# Button.net
KiCad netlist of a schematic drawn in EAGLE
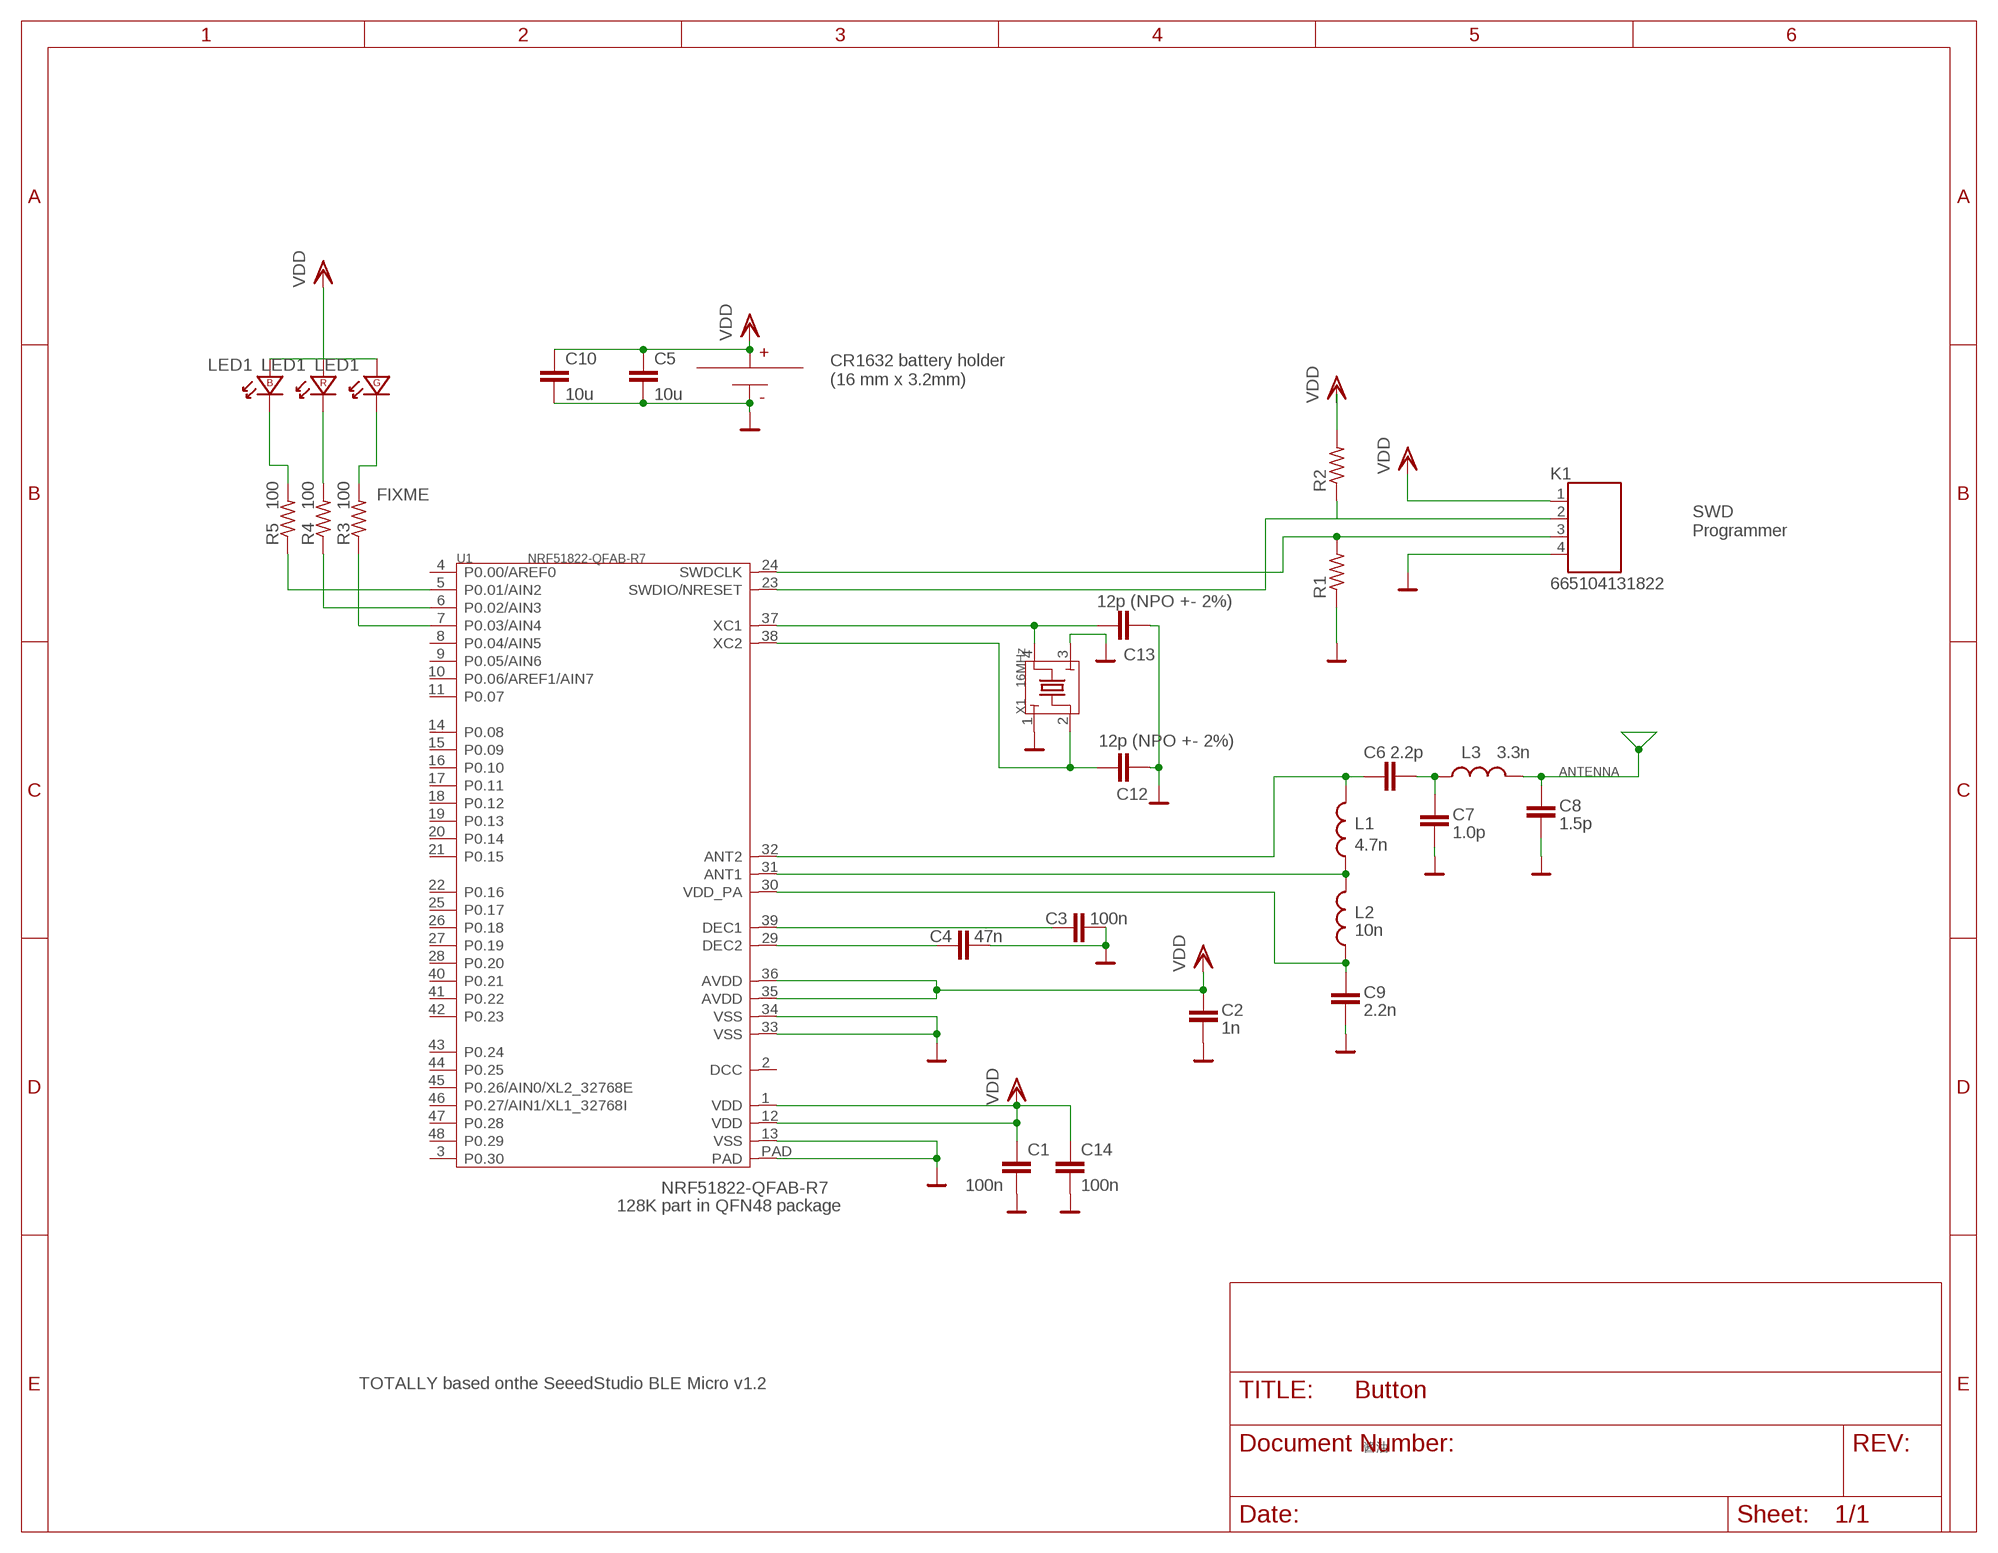
[diagram p0: schematic, sheet 1]

(export (version "E")
  (design (tool "Eeschema 10.0.6"))
  (components
    (comp (ref "B1")
      (value "CON-COINCEL-HOLDER-KEYSTONE-3012TR")
      (footprint "eagle-import:16MM-COINCELL-KEYSTONE")
      (libsource (lib "eagle-import") (part "CON-COINCEL-HOLDER-KEYSTONE-3012TR"))
    )
    (comp (ref "C1")
      (value "100n")
      (footprint "eagle-import:.0402-C-NOSILK")
      (libsource (lib "eagle-import") (part "C-EU0402-C-NOSILK"))
    )
    (comp (ref "C2")
      (value "1n")
      (footprint "eagle-import:.0402-C-NOSILK")
      (libsource (lib "eagle-import") (part "C-EU0402-C-NOSILK"))
    )
    (comp (ref "C3")
      (value "100n")
      (footprint "eagle-import:.0402-C-NOSILK")
      (libsource (lib "eagle-import") (part "C-EU0402-C-NOSILK"))
    )
    (comp (ref "C4")
      (value "47n")
      (footprint "eagle-import:.0402-C-NOSILK")
      (libsource (lib "eagle-import") (part "C-EU0402-C-NOSILK"))
    )
    (comp (ref "C5")
      (value "10u")
      (footprint "eagle-import:.0805-B-NOSILK")
      (libsource (lib "eagle-import") (part "C-EU0805-B-NOSILK"))
    )
    (comp (ref "C6")
      (value "2.2p")
      (footprint "eagle-import:.0402-C-NOSILK")
      (libsource (lib "eagle-import") (part "C-EU0402-C-NOSILK"))
    )
    (comp (ref "C7")
      (value "1.0p")
      (footprint "eagle-import:.0402-C-NOSILK")
      (libsource (lib "eagle-import") (part "C-EU0402-C-NOSILK"))
    )
    (comp (ref "C8")
      (value "1.5p")
      (footprint "eagle-import:.0402-C-NOSILK")
      (libsource (lib "eagle-import") (part "C-EU0402-C-NOSILK"))
    )
    (comp (ref "C9")
      (value "2.2n")
      (footprint "eagle-import:.0402-C-NOSILK")
      (libsource (lib "eagle-import") (part "C-EU0402-C-NOSILK"))
    )
    (comp (ref "C10")
      (value "10u")
      (footprint "eagle-import:.0805-B-NOSILK")
      (libsource (lib "eagle-import") (part "C-EU0805-B-NOSILK"))
    )
    (comp (ref "C12")
      (value "12p (NPO +- 2%)")
      (footprint "eagle-import:.0402-C-NOSILK")
      (libsource (lib "eagle-import") (part "C-EU0402-C-NOSILK"))
    )
    (comp (ref "C13")
      (value "12p (NPO +- 2%)")
      (footprint "eagle-import:.0402-C-NOSILK")
      (libsource (lib "eagle-import") (part "C-EU0402-C-NOSILK"))
    )
    (comp (ref "C14")
      (value "100n")
      (footprint "eagle-import:.0402-C-NOSILK")
      (libsource (lib "eagle-import") (part "C-EU0402-C-NOSILK"))
    )
    (comp (ref "K1")
      (value "665104131822")
      (footprint "eagle-import:665104131822")
      (libsource (lib "eagle-import") (part "665104131822"))
    )
    (comp (ref "L1")
      (value "4.7n")
      (footprint "eagle-import:.0402-C-NOSILK")
      (libsource (lib "eagle-import") (part "L-US0402-C-NOSILK"))
    )
    (comp (ref "L2")
      (value "10n")
      (footprint "eagle-import:.0402-C-NOSILK")
      (libsource (lib "eagle-import") (part "L-US0402-C-NOSILK"))
    )
    (comp (ref "L3")
      (value "3.3n")
      (footprint "eagle-import:.0402-C-NOSILK")
      (libsource (lib "eagle-import") (part "L-US0402-C-NOSILK"))
    )
    (comp (ref "LED1")
      (value "LED-RGB-SEPARATE-3528")
      (footprint "eagle-import:LED-3528")
      (libsource (lib "eagle-import") (part "LED-RGB-SEPARATE-3528"))
    )
    (comp (ref "R1")
      (value "R-US_R0402")
      (footprint "eagle-import:R0402")
      (libsource (lib "eagle-import") (part "R-US_R0402"))
    )
    (comp (ref "R2")
      (value "R-US_R0402")
      (footprint "eagle-import:R0402")
      (libsource (lib "eagle-import") (part "R-US_R0402"))
    )
    (comp (ref "R3")
      (value "100")
      (footprint "eagle-import:.0402-C-NOSILK")
      (libsource (lib "eagle-import") (part "R-US_0402-C-NOSILK"))
    )
    (comp (ref "R4")
      (value "100")
      (footprint "eagle-import:.0402-C-NOSILK")
      (libsource (lib "eagle-import") (part "R-US_0402-C-NOSILK"))
    )
    (comp (ref "R5")
      (value "100")
      (footprint "eagle-import:.0402-C-NOSILK")
      (libsource (lib "eagle-import") (part "R-US_0402-C-NOSILK"))
    )
    (comp (ref "U1")
      (value "NRF51822-QFAB-R7")
      (footprint "eagle-import:QFN48-6X6MM")
      (libsource (lib "eagle-import") (part "NRF51822"))
    )
    (comp (ref "X1")
      (value "16MHz")
      (footprint "eagle-import:2520")
      (libsource (lib "eagle-import") (part "CRYSTAL'-2520'"))
    )
  )
  (nets
    (net (code "1") (name "/ANTENNA") (class "Default")
      (node (ref "C8") (pin "2") (pinfunction "2_2") (pintype "passive"))
      (node (ref "L3") (pin "2") (pinfunction "2_2") (pintype "passive"))
    )
    (net (code "2") (name "GND") (class "Default")
      (node (ref "B1") (pin "NEG") (pinfunction "NEG_NEG") (pintype "power_in"))
      (node (ref "C1") (pin "2") (pinfunction "2_2") (pintype "passive"))
      (node (ref "C10") (pin "2") (pinfunction "2_2") (pintype "passive"))
      (node (ref "C12") (pin "2") (pinfunction "2_2") (pintype "passive"))
      (node (ref "C13") (pin "2") (pinfunction "2_2") (pintype "passive"))
      (node (ref "C14") (pin "2") (pinfunction "2_2") (pintype "passive"))
      (node (ref "C2") (pin "2") (pinfunction "2_2") (pintype "passive"))
      (node (ref "C3") (pin "2") (pinfunction "2_2") (pintype "passive"))
      (node (ref "C4") (pin "2") (pinfunction "2_2") (pintype "passive"))
      (node (ref "C5") (pin "2") (pinfunction "2_2") (pintype "passive"))
      (node (ref "C7") (pin "1") (pinfunction "1_1") (pintype "passive"))
      (node (ref "C8") (pin "1") (pinfunction "1_1") (pintype "passive"))
      (node (ref "C9") (pin "2") (pinfunction "2_2") (pintype "passive"))
      (node (ref "K1") (pin "4") (pinfunction "4_4") (pintype "passive"))
      (node (ref "R1") (pin "1") (pinfunction "1_1") (pintype "passive"))
      (node (ref "U1") (pin "13") (pinfunction "VSS_13") (pintype "bidirectional"))
      (node (ref "U1") (pin "33") (pinfunction "VSS_33") (pintype "bidirectional"))
      (node (ref "U1") (pin "34") (pinfunction "VSS_34") (pintype "bidirectional"))
      (node (ref "U1") (pin "PAD") (pinfunction "PAD_PAD") (pintype "bidirectional"))
      (node (ref "X1") (pin "1") (pinfunction "1_1") (pintype "bidirectional"))
      (node (ref "X1") (pin "3") (pinfunction "3_3") (pintype "bidirectional"))
    )
    (net (code "3") (name "Net-(C6-Pad2)") (class "Default")
      (node (ref "C6") (pin "2") (pinfunction "2_2") (pintype "passive"))
      (node (ref "C7") (pin "2") (pinfunction "2_2") (pintype "passive"))
      (node (ref "L3") (pin "1") (pinfunction "1_1") (pintype "passive"))
    )
    (net (code "4") (name "Net-(LED1A-K)") (class "Default")
      (node (ref "LED1") (pin "6") (pinfunction "K_6") (pintype "passive"))
      (node (ref "R5") (pin "2") (pinfunction "2_2") (pintype "passive"))
    )
    (net (code "5") (name "Net-(LED1B-K)") (class "Default")
      (node (ref "LED1") (pin "4") (pinfunction "K_4") (pintype "passive"))
      (node (ref "R3") (pin "2") (pinfunction "2_2") (pintype "passive"))
    )
    (net (code "6") (name "Net-(LED1C-K)") (class "Default")
      (node (ref "LED1") (pin "5") (pinfunction "K_5") (pintype "passive"))
      (node (ref "R4") (pin "2") (pinfunction "2_2") (pintype "passive"))
    )
    (net (code "7") (name "Net-(U1-ANT1)") (class "Default")
      (node (ref "L1") (pin "1") (pinfunction "1_1") (pintype "passive"))
      (node (ref "L2") (pin "2") (pinfunction "2_2") (pintype "passive"))
      (node (ref "U1") (pin "31") (pinfunction "ANT1_31") (pintype "bidirectional"))
    )
    (net (code "8") (name "Net-(U1-ANT2)") (class "Default")
      (node (ref "C6") (pin "1") (pinfunction "1_1") (pintype "passive"))
      (node (ref "L1") (pin "2") (pinfunction "2_2") (pintype "passive"))
      (node (ref "U1") (pin "32") (pinfunction "ANT2_32") (pintype "bidirectional"))
    )
    (net (code "9") (name "Net-(U1-DEC1)") (class "Default")
      (node (ref "C3") (pin "1") (pinfunction "1_1") (pintype "passive"))
      (node (ref "U1") (pin "39") (pinfunction "DEC1_39") (pintype "bidirectional"))
    )
    (net (code "10") (name "Net-(U1-DEC2)") (class "Default")
      (node (ref "C4") (pin "1") (pinfunction "1_1") (pintype "passive"))
      (node (ref "U1") (pin "29") (pinfunction "DEC2_29") (pintype "bidirectional"))
    )
    (net (code "11") (name "Net-(U1-P0.01{slash}AIN2)") (class "Default")
      (node (ref "R5") (pin "1") (pinfunction "1_1") (pintype "passive"))
      (node (ref "U1") (pin "5") (pinfunction "P0.01/AIN2_5") (pintype "bidirectional"))
    )
    (net (code "12") (name "Net-(U1-P0.02{slash}AIN3)") (class "Default")
      (node (ref "R4") (pin "1") (pinfunction "1_1") (pintype "passive"))
      (node (ref "U1") (pin "6") (pinfunction "P0.02/AIN3_6") (pintype "bidirectional"))
    )
    (net (code "13") (name "Net-(U1-P0.03{slash}AIN4)") (class "Default")
      (node (ref "R3") (pin "1") (pinfunction "1_1") (pintype "passive"))
      (node (ref "U1") (pin "7") (pinfunction "P0.03/AIN4_7") (pintype "bidirectional"))
    )
    (net (code "14") (name "Net-(U1-SWDCLK)") (class "Default")
      (node (ref "K1") (pin "3") (pinfunction "3_3") (pintype "passive"))
      (node (ref "R1") (pin "2") (pinfunction "2_2") (pintype "passive"))
      (node (ref "U1") (pin "24") (pinfunction "SWDCLK_24") (pintype "bidirectional"))
    )
    (net (code "15") (name "Net-(U1-SWDIO{slash}NRESET)") (class "Default")
      (node (ref "K1") (pin "2") (pinfunction "2_2") (pintype "passive"))
      (node (ref "R2") (pin "1") (pinfunction "1_1") (pintype "passive"))
      (node (ref "U1") (pin "23") (pinfunction "SWDIO/NRESET_23") (pintype "bidirectional"))
    )
    (net (code "16") (name "Net-(U1-VDD_PA)") (class "Default")
      (node (ref "C9") (pin "1") (pinfunction "1_1") (pintype "passive"))
      (node (ref "L2") (pin "1") (pinfunction "1_1") (pintype "passive"))
      (node (ref "U1") (pin "30") (pinfunction "VDD_PA_30") (pintype "bidirectional"))
    )
    (net (code "17") (name "Net-(U1-XC1)") (class "Default")
      (node (ref "C13") (pin "1") (pinfunction "1_1") (pintype "passive"))
      (node (ref "U1") (pin "37") (pinfunction "XC1_37") (pintype "bidirectional"))
      (node (ref "X1") (pin "4") (pinfunction "4_4") (pintype "passive"))
    )
    (net (code "18") (name "Net-(U1-XC2)") (class "Default")
      (node (ref "C12") (pin "1") (pinfunction "1_1") (pintype "passive"))
      (node (ref "U1") (pin "38") (pinfunction "XC2_38") (pintype "bidirectional"))
      (node (ref "X1") (pin "2") (pinfunction "2_2") (pintype "passive"))
    )
    (net (code "19") (name "VDD") (class "Default")
      (node (ref "B1") (pin "POS@1") (pinfunction "POS_POS@1") (pintype "power_in"))
      (node (ref "B1") (pin "POS@2") (pinfunction "POS_POS@2") (pintype "power_in"))
      (node (ref "C1") (pin "1") (pinfunction "1_1") (pintype "passive"))
      (node (ref "C10") (pin "1") (pinfunction "1_1") (pintype "passive"))
      (node (ref "C14") (pin "1") (pinfunction "1_1") (pintype "passive"))
      (node (ref "C2") (pin "1") (pinfunction "1_1") (pintype "passive"))
      (node (ref "C5") (pin "1") (pinfunction "1_1") (pintype "passive"))
      (node (ref "K1") (pin "1") (pinfunction "1_1") (pintype "passive"))
      (node (ref "LED1") (pin "1") (pinfunction "A_1") (pintype "passive"))
      (node (ref "LED1") (pin "2") (pinfunction "A_2") (pintype "passive"))
      (node (ref "LED1") (pin "3") (pinfunction "A_3") (pintype "passive"))
      (node (ref "U1") (pin "1") (pinfunction "VDD_1") (pintype "bidirectional"))
      (node (ref "U1") (pin "12") (pinfunction "VDD_12") (pintype "bidirectional"))
      (node (ref "U1") (pin "35") (pinfunction "AVDD_35") (pintype "bidirectional"))
      (node (ref "U1") (pin "36") (pinfunction "AVDD_36") (pintype "bidirectional"))
    )
    (net (code "20") (name "unconnected-(R2-Pad2)") (class "Default")
      (node (ref "R2") (pin "2") (pinfunction "2_2") (pintype "passive"))
    )
    (net (code "21") (name "unconnected-(U1-DCC-Pad2)") (class "Default")
      (node (ref "U1") (pin "2") (pinfunction "DCC_2") (pintype "bidirectional"))
    )
    (net (code "22") (name "unconnected-(U1-P0.00{slash}AREF0-Pad4)") (class "Default")
      (node (ref "U1") (pin "4") (pinfunction "P0.00/AREF0_4") (pintype "bidirectional"))
    )
    (net (code "23") (name "unconnected-(U1-P0.04{slash}AIN5-Pad8)") (class "Default")
      (node (ref "U1") (pin "8") (pinfunction "P0.04/AIN5_8") (pintype "bidirectional"))
    )
    (net (code "24") (name "unconnected-(U1-P0.05{slash}AIN6-Pad9)") (class "Default")
      (node (ref "U1") (pin "9") (pinfunction "P0.05/AIN6_9") (pintype "bidirectional"))
    )
    (net (code "25") (name "unconnected-(U1-P0.06{slash}AREF1{slash}AIN7-Pad10)") (class "Default")
      (node (ref "U1") (pin "10") (pinfunction "P0.06/AREF1/AIN7_10") (pintype "bidirectional"))
    )
    (net (code "26") (name "unconnected-(U1-P0.07-Pad11)") (class "Default")
      (node (ref "U1") (pin "11") (pinfunction "P0.07_11") (pintype "bidirectional"))
    )
    (net (code "27") (name "unconnected-(U1-P0.08-Pad14)") (class "Default")
      (node (ref "U1") (pin "14") (pinfunction "P0.08_14") (pintype "bidirectional"))
    )
    (net (code "28") (name "unconnected-(U1-P0.09-Pad15)") (class "Default")
      (node (ref "U1") (pin "15") (pinfunction "P0.09_15") (pintype "bidirectional"))
    )
    (net (code "29") (name "unconnected-(U1-P0.10-Pad16)") (class "Default")
      (node (ref "U1") (pin "16") (pinfunction "P0.10_16") (pintype "bidirectional"))
    )
    (net (code "30") (name "unconnected-(U1-P0.11-Pad17)") (class "Default")
      (node (ref "U1") (pin "17") (pinfunction "P0.11_17") (pintype "bidirectional"))
    )
    (net (code "31") (name "unconnected-(U1-P0.12-Pad18)") (class "Default")
      (node (ref "U1") (pin "18") (pinfunction "P0.12_18") (pintype "bidirectional"))
    )
    (net (code "32") (name "unconnected-(U1-P0.13-Pad19)") (class "Default")
      (node (ref "U1") (pin "19") (pinfunction "P0.13_19") (pintype "bidirectional"))
    )
    (net (code "33") (name "unconnected-(U1-P0.14-Pad20)") (class "Default")
      (node (ref "U1") (pin "20") (pinfunction "P0.14_20") (pintype "bidirectional"))
    )
    (net (code "34") (name "unconnected-(U1-P0.15-Pad21)") (class "Default")
      (node (ref "U1") (pin "21") (pinfunction "P0.15_21") (pintype "bidirectional"))
    )
    (net (code "35") (name "unconnected-(U1-P0.16-Pad22)") (class "Default")
      (node (ref "U1") (pin "22") (pinfunction "P0.16_22") (pintype "bidirectional"))
    )
    (net (code "36") (name "unconnected-(U1-P0.17-Pad25)") (class "Default")
      (node (ref "U1") (pin "25") (pinfunction "P0.17_25") (pintype "bidirectional"))
    )
    (net (code "37") (name "unconnected-(U1-P0.18-Pad26)") (class "Default")
      (node (ref "U1") (pin "26") (pinfunction "P0.18_26") (pintype "bidirectional"))
    )
    (net (code "38") (name "unconnected-(U1-P0.19-Pad27)") (class "Default")
      (node (ref "U1") (pin "27") (pinfunction "P0.19_27") (pintype "bidirectional"))
    )
    (net (code "39") (name "unconnected-(U1-P0.20-Pad28)") (class "Default")
      (node (ref "U1") (pin "28") (pinfunction "P0.20_28") (pintype "bidirectional"))
    )
    (net (code "40") (name "unconnected-(U1-P0.21-Pad40)") (class "Default")
      (node (ref "U1") (pin "40") (pinfunction "P0.21_40") (pintype "bidirectional"))
    )
    (net (code "41") (name "unconnected-(U1-P0.22-Pad41)") (class "Default")
      (node (ref "U1") (pin "41") (pinfunction "P0.22_41") (pintype "bidirectional"))
    )
    (net (code "42") (name "unconnected-(U1-P0.23-Pad42)") (class "Default")
      (node (ref "U1") (pin "42") (pinfunction "P0.23_42") (pintype "bidirectional"))
    )
    (net (code "43") (name "unconnected-(U1-P0.24-Pad43)") (class "Default")
      (node (ref "U1") (pin "43") (pinfunction "P0.24_43") (pintype "bidirectional"))
    )
    (net (code "44") (name "unconnected-(U1-P0.25-Pad44)") (class "Default")
      (node (ref "U1") (pin "44") (pinfunction "P0.25_44") (pintype "bidirectional"))
    )
    (net (code "45") (name "unconnected-(U1-P0.26{slash}AIN0{slash}XL2_32768E-Pad45)") (class "Default")
      (node (ref "U1") (pin "45") (pinfunction "P0.26/AIN0/XL2_32768E_45") (pintype "bidirectional"))
    )
    (net (code "46") (name "unconnected-(U1-P0.27{slash}AIN1{slash}XL1_32768I-Pad46)") (class "Default")
      (node (ref "U1") (pin "46") (pinfunction "P0.27/AIN1/XL1_32768I_46") (pintype "bidirectional"))
    )
    (net (code "47") (name "unconnected-(U1-P0.28-Pad47)") (class "Default")
      (node (ref "U1") (pin "47") (pinfunction "P0.28_47") (pintype "bidirectional"))
    )
    (net (code "48") (name "unconnected-(U1-P0.29-Pad48)") (class "Default")
      (node (ref "U1") (pin "48") (pinfunction "P0.29_48") (pintype "bidirectional"))
    )
    (net (code "49") (name "unconnected-(U1-P0.30-Pad3)") (class "Default")
      (node (ref "U1") (pin "3") (pinfunction "P0.30_3") (pintype "bidirectional"))
    )
  )
)
